# eth_part.net
KiCad netlist of a schematic drawn in Altium Designer
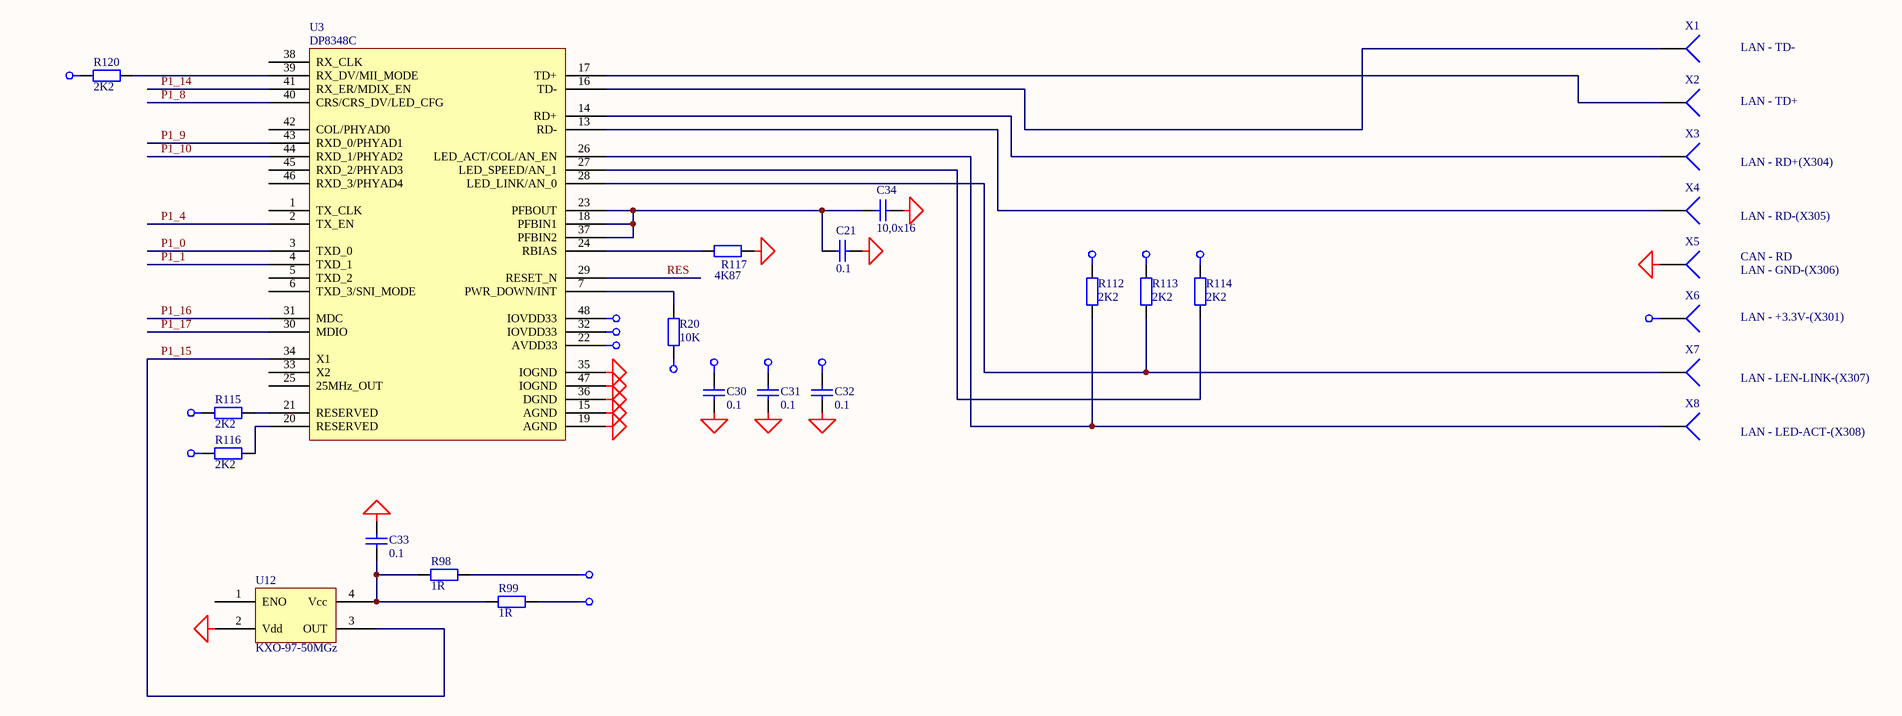
[diagram p0: eth_part.SchDoc]

(export (version "E")
  (design (tool "Eeschema 10.0.6"))
  (components
    (comp (ref "C21")
      (value "0.1")
      (footprint "C3216-1206")
      (description "Capacitor (Semiconductor SIM Model)")
      (fields (field (name "MANUFACTURER") "Generic Components") (field (name "PUBLISHER") "Altium Limited"))
      (libsource (lib "Miscellaneous Devices") (part "Cap Semi"))
    )
    (comp (ref "C30")
      (value "0.1")
      (footprint "_1206")
      (description "Capacitor (Semiconductor SIM Model)")
      (fields (field (name "MANUFACTURER") "Generic Components") (field (name "PUBLISHER") "Altium Limited"))
      (libsource (lib "Miscellaneous Devices") (part "Cap Semi"))
    )
    (comp (ref "C31")
      (value "0.1")
      (footprint "_1206")
      (description "Capacitor (Semiconductor SIM Model)")
      (fields (field (name "MANUFACTURER") "Generic Components") (field (name "PUBLISHER") "Altium Limited"))
      (libsource (lib "Miscellaneous Devices") (part "Cap Semi"))
    )
    (comp (ref "C32")
      (value "0.1")
      (footprint "_1206")
      (description "Capacitor (Semiconductor SIM Model)")
      (fields (field (name "MANUFACTURER") "Generic Components") (field (name "PUBLISHER") "Altium Limited"))
      (libsource (lib "Miscellaneous Devices") (part "Cap Semi"))
    )
    (comp (ref "C33")
      (value "0.1")
      (footprint "_1206")
      (description "Capacitor (Semiconductor SIM Model)")
      (fields (field (name "MANUFACTURER") "Generic Components") (field (name "PUBLISHER") "Altium Limited"))
      (libsource (lib "Miscellaneous Devices") (part "Cap Semi"))
    )
    (comp (ref "C34")
      (value "10,0x16")
      (footprint "C3216-1206")
      (description "Capacitor (Semiconductor SIM Model)")
      (fields (field (name "MANUFACTURER") "Generic Components") (field (name "PUBLISHER") "Altium Limited"))
      (libsource (lib "Miscellaneous Devices") (part "Cap Semi"))
    )
    (comp (ref "R20")
      (value "10K")
      (footprint "_1206")
      (description "Resistor")
      (fields (field (name "MANUFACTURER") "Generic Components") (field (name "PUBLISHER") "Altium Limited"))
      (libsource (lib "") (part "Res2_3"))
    )
    (comp (ref "R98")
      (value "1R")
      (footprint "_1206")
      (description "Resistor")
      (fields (field (name "MANUFACTURER") "Generic Components") (field (name "PUBLISHER") "Altium Limited"))
      (libsource (lib "") (part "Res2_2"))
    )
    (comp (ref "R99")
      (value "1R")
      (footprint "_1206")
      (description "Resistor")
      (fields (field (name "MANUFACTURER") "Generic Components") (field (name "PUBLISHER") "Altium Limited"))
      (libsource (lib "") (part "Res2_2"))
    )
    (comp (ref "R112")
      (value "2K2")
      (footprint "_1206")
      (description "Resistor")
      (fields (field (name "MANUFACTURER") "Generic Components") (field (name "PUBLISHER") "Altium Limited"))
      (libsource (lib "Miscellaneous Devices") (part "Res2"))
    )
    (comp (ref "R113")
      (value "2K2")
      (footprint "_1206")
      (description "Resistor")
      (fields (field (name "MANUFACTURER") "Generic Components") (field (name "PUBLISHER") "Altium Limited"))
      (libsource (lib "Miscellaneous Devices") (part "Res2"))
    )
    (comp (ref "R114")
      (value "2K2")
      (footprint "_1206")
      (description "Resistor")
      (fields (field (name "MANUFACTURER") "Generic Components") (field (name "PUBLISHER") "Altium Limited"))
      (libsource (lib "Miscellaneous Devices") (part "Res2"))
    )
    (comp (ref "R115")
      (value "2K2")
      (footprint "_1206")
      (description "Resistor")
      (fields (field (name "MANUFACTURER") "Generic Components") (field (name "PUBLISHER") "Altium Limited"))
      (libsource (lib "") (part "Res2_1"))
    )
    (comp (ref "R116")
      (value "2K2")
      (footprint "_1206")
      (description "Resistor")
      (fields (field (name "MANUFACTURER") "Generic Components") (field (name "PUBLISHER") "Altium Limited"))
      (libsource (lib "") (part "Res2_1"))
    )
    (comp (ref "R117")
      (value "4K87")
      (footprint "_1206")
      (description "Resistor")
      (fields (field (name "MANUFACTURER") "Generic Components") (field (name "PUBLISHER") "Altium Limited"))
      (libsource (lib "") (part "Res2_1"))
    )
    (comp (ref "R120")
      (value "2K2")
      (footprint "_1206")
      (description "Resistor")
      (fields (field (name "MANUFACTURER") "Generic Components") (field (name "PUBLISHER") "Altium Limited"))
      (libsource (lib "") (part "Res2_1"))
    )
    (comp (ref "U3") (value "DP8348C") (footprint "F-QFP7X7-G48/N") (libsource (lib "PAL") (part "DP8348C")))
    (comp (ref "U12") (value "KXO-97-50MGz") (footprint "KXO-97") (libsource (lib "PAL") (part "KXO-97")))
    (comp (ref "X1")
      (value "~")
      (footprint "PIN1")
      (description "Socket")
      (fields (field (name "MANUFACTURER") "Generic Components") (field (name "PUBLISHER") "Altium Limited"))
      (libsource (lib "Miscellaneous Connectors") (part "Socket"))
    )
    (comp (ref "X2")
      (value "~")
      (footprint "PIN1")
      (description "Socket")
      (fields (field (name "MANUFACTURER") "Generic Components") (field (name "PUBLISHER") "Altium Limited"))
      (libsource (lib "Miscellaneous Connectors") (part "Socket"))
    )
    (comp (ref "X3")
      (value "~")
      (footprint "PIN1")
      (description "Socket")
      (fields (field (name "MANUFACTURER") "Generic Components") (field (name "PUBLISHER") "Altium Limited"))
      (libsource (lib "Miscellaneous Connectors") (part "Socket"))
    )
    (comp (ref "X4")
      (value "~")
      (footprint "PIN1")
      (description "Socket")
      (fields (field (name "MANUFACTURER") "Generic Components") (field (name "PUBLISHER") "Altium Limited"))
      (libsource (lib "Miscellaneous Connectors") (part "Socket"))
    )
    (comp (ref "X5")
      (value "~")
      (footprint "PIN1")
      (description "Socket")
      (fields (field (name "MANUFACTURER") "Generic Components") (field (name "PUBLISHER") "Altium Limited"))
      (libsource (lib "Miscellaneous Connectors") (part "Socket"))
    )
    (comp (ref "X6")
      (value "~")
      (footprint "PIN1")
      (description "Socket")
      (fields (field (name "MANUFACTURER") "Generic Components") (field (name "PUBLISHER") "Altium Limited"))
      (libsource (lib "Miscellaneous Connectors") (part "Socket"))
    )
    (comp (ref "X7")
      (value "~")
      (footprint "PIN1")
      (description "Socket")
      (fields (field (name "MANUFACTURER") "Generic Components") (field (name "PUBLISHER") "Altium Limited"))
      (libsource (lib "Miscellaneous Connectors") (part "Socket"))
    )
    (comp (ref "X8")
      (value "~")
      (footprint "PIN1")
      (description "Socket")
      (fields (field (name "MANUFACTURER") "Generic Components") (field (name "PUBLISHER") "Altium Limited"))
      (libsource (lib "Miscellaneous Connectors") (part "Socket"))
    )
  )
  (nets
    (net (code "1") (name "+3v3") (class "Default")
      (node (ref "C30") (pin "1") (pinfunction "1_1") (pintype "passive"))
      (node (ref "C31") (pin "1") (pinfunction "1_1") (pintype "passive"))
      (node (ref "C32") (pin "1") (pinfunction "1_1") (pintype "passive"))
      (node (ref "R112") (pin "2") (pinfunction "2_2") (pintype "passive"))
      (node (ref "R113") (pin "2") (pinfunction "2_2") (pintype "passive"))
      (node (ref "R114") (pin "2") (pinfunction "2_2") (pintype "passive"))
      (node (ref "R115") (pin "2") (pinfunction "2_2") (pintype "passive"))
      (node (ref "R116") (pin "2") (pinfunction "2_2") (pintype "passive"))
      (node (ref "R120") (pin "2") (pinfunction "2_2") (pintype "passive"))
      (node (ref "R20") (pin "2") (pinfunction "2_2") (pintype "passive"))
      (node (ref "R99") (pin "2") (pinfunction "2_2") (pintype "passive"))
      (node (ref "U3") (pin "22") (pinfunction "AVDD33_22") (pintype "passive"))
      (node (ref "U3") (pin "32") (pinfunction "IOVDD33_32") (pintype "passive"))
      (node (ref "U3") (pin "48") (pinfunction "IOVDD33_48") (pintype "passive"))
      (node (ref "X6") (pin "1") (pinfunction "1_1") (pintype "passive"))
    )
    (net (code "2") (name "+5v") (class "Default")
      (node (ref "R98") (pin "2") (pinfunction "2_2") (pintype "passive"))
    )
    (net (code "3") (name "/P1_0") (class "Default")
      (node (ref "U3") (pin "3") (pinfunction "TXD_0_3") (pintype "passive"))
    )
    (net (code "4") (name "/P1_1") (class "Default")
      (node (ref "U3") (pin "4") (pinfunction "TXD_1_4") (pintype "passive"))
    )
    (net (code "5") (name "/P1_4") (class "Default")
      (node (ref "U3") (pin "2") (pinfunction "TX_EN_2") (pintype "passive"))
    )
    (net (code "6") (name "/P1_8") (class "Default")
      (node (ref "U3") (pin "40") (pinfunction "CRS/CRS_DV/LED_CFG_40") (pintype "passive"))
    )
    (net (code "7") (name "/P1_9") (class "Default")
      (node (ref "U3") (pin "43") (pinfunction "RXD_0/PHYAD1_43") (pintype "passive"))
    )
    (net (code "8") (name "/P1_10") (class "Default")
      (node (ref "U3") (pin "44") (pinfunction "RXD_1/PHYAD2_44") (pintype "passive"))
    )
    (net (code "9") (name "/P1_14") (class "Default")
      (node (ref "U3") (pin "41") (pinfunction "RX_ER/MDIX_EN_41") (pintype "passive"))
    )
    (net (code "10") (name "/P1_15") (class "Default")
      (node (ref "U12") (pin "3") (pinfunction "OUT_3") (pintype "passive"))
      (node (ref "U3") (pin "34") (pinfunction "X1_34") (pintype "passive"))
    )
    (net (code "11") (name "/P1_16") (class "Default")
      (node (ref "U3") (pin "31") (pinfunction "MDC_31") (pintype "passive"))
    )
    (net (code "12") (name "/P1_17") (class "Default")
      (node (ref "U3") (pin "30") (pinfunction "MDIO_30") (pintype "passive"))
    )
    (net (code "13") (name "/RES") (class "Default")
      (node (ref "U3") (pin "29") (pinfunction "RESET_N_29") (pintype "passive"))
    )
    (net (code "14") (name "GND") (class "Default")
      (node (ref "C21") (pin "2") (pinfunction "2_2") (pintype "passive"))
      (node (ref "C30") (pin "2") (pinfunction "2_2") (pintype "passive"))
      (node (ref "C31") (pin "2") (pinfunction "2_2") (pintype "passive"))
      (node (ref "C32") (pin "2") (pinfunction "2_2") (pintype "passive"))
      (node (ref "C33") (pin "2") (pinfunction "2_2") (pintype "passive"))
      (node (ref "C34") (pin "2") (pinfunction "2_2") (pintype "passive"))
      (node (ref "R117") (pin "1") (pinfunction "1_1") (pintype "passive"))
      (node (ref "U12") (pin "2") (pinfunction "Vdd_2") (pintype "passive"))
      (node (ref "U3") (pin "15") (pinfunction "AGND_15") (pintype "passive"))
      (node (ref "U3") (pin "19") (pinfunction "AGND_19") (pintype "passive"))
      (node (ref "U3") (pin "35") (pinfunction "IOGND_35") (pintype "passive"))
      (node (ref "U3") (pin "36") (pinfunction "DGND_36") (pintype "passive"))
      (node (ref "U3") (pin "47") (pinfunction "IOGND_47") (pintype "passive"))
      (node (ref "X5") (pin "1") (pinfunction "1_1") (pintype "passive"))
    )
    (net (code "15") (name "Net-(R115-Pad1)") (class "Default")
      (node (ref "R115") (pin "1") (pinfunction "1_1") (pintype "passive"))
      (node (ref "U3") (pin "21") (pinfunction "RESERVED_21") (pintype "passive"))
    )
    (net (code "16") (name "Net-(R116-Pad1)") (class "Default")
      (node (ref "R116") (pin "1") (pinfunction "1_1") (pintype "passive"))
      (node (ref "U3") (pin "20") (pinfunction "RESERVED_20") (pintype "passive"))
    )
    (net (code "17") (name "Net-(U3-LED_ACT{slash}COL{slash}AN_EN)") (class "Default")
      (node (ref "R112") (pin "1") (pinfunction "1_1") (pintype "passive"))
      (node (ref "U3") (pin "26") (pinfunction "LED_ACT/COL/AN_EN_26") (pintype "passive"))
      (node (ref "X8") (pin "1") (pinfunction "1_1") (pintype "passive"))
    )
    (net (code "18") (name "Net-(U3-LED_LINK{slash}AN_0)") (class "Default")
      (node (ref "R113") (pin "1") (pinfunction "1_1") (pintype "passive"))
      (node (ref "U3") (pin "28") (pinfunction "LED_LINK/AN_0_28") (pintype "passive"))
      (node (ref "X7") (pin "1") (pinfunction "1_1") (pintype "passive"))
    )
    (net (code "19") (name "Net-(U3-LED_SPEED{slash}AN_1)") (class "Default")
      (node (ref "R114") (pin "1") (pinfunction "1_1") (pintype "passive"))
      (node (ref "U3") (pin "27") (pinfunction "LED_SPEED/AN_1_27") (pintype "passive"))
    )
    (net (code "20") (name "Net-(U3-PFBIN1)") (class "Default")
      (node (ref "C21") (pin "1") (pinfunction "1_1") (pintype "passive"))
      (node (ref "C34") (pin "1") (pinfunction "1_1") (pintype "passive"))
      (node (ref "U3") (pin "18") (pinfunction "PFBIN1_18") (pintype "passive"))
      (node (ref "U3") (pin "23") (pinfunction "PFBOUT_23") (pintype "passive"))
      (node (ref "U3") (pin "37") (pinfunction "PFBIN2_37") (pintype "passive"))
    )
    (net (code "21") (name "Net-(U3-PWR_DOWN{slash}INT)") (class "Default")
      (node (ref "R20") (pin "1") (pinfunction "1_1") (pintype "passive"))
      (node (ref "U3") (pin "7") (pinfunction "PWR_DOWN/INT_7") (pintype "passive"))
    )
    (net (code "22") (name "Net-(U3-RBIAS)") (class "Default")
      (node (ref "R117") (pin "2") (pinfunction "2_2") (pintype "passive"))
      (node (ref "U3") (pin "24") (pinfunction "RBIAS_24") (pintype "passive"))
    )
    (net (code "23") (name "Net-(U3-RD+)") (class "Default")
      (node (ref "U3") (pin "14") (pinfunction "RD+_14") (pintype "passive"))
      (node (ref "X3") (pin "1") (pinfunction "1_1") (pintype "passive"))
    )
    (net (code "24") (name "Net-(U3-RD-)") (class "Default")
      (node (ref "U3") (pin "13") (pinfunction "RD-_13") (pintype "passive"))
      (node (ref "X4") (pin "1") (pinfunction "1_1") (pintype "passive"))
    )
    (net (code "25") (name "Net-(U3-RX_DV{slash}MII_MODE)") (class "Default")
      (node (ref "R120") (pin "1") (pinfunction "1_1") (pintype "passive"))
      (node (ref "U3") (pin "39") (pinfunction "RX_DV/MII_MODE_39") (pintype "passive"))
    )
    (net (code "26") (name "Net-(U3-TD+)") (class "Default")
      (node (ref "U3") (pin "17") (pinfunction "TD+_17") (pintype "passive"))
      (node (ref "X2") (pin "1") (pinfunction "1_1") (pintype "passive"))
    )
    (net (code "27") (name "Net-(U3-TD-)") (class "Default")
      (node (ref "U3") (pin "16") (pinfunction "TD-_16") (pintype "passive"))
      (node (ref "X1") (pin "1") (pinfunction "1_1") (pintype "passive"))
    )
    (net (code "28") (name "Net-(U12-Vcc)") (class "Default")
      (node (ref "C33") (pin "1") (pinfunction "1_1") (pintype "passive"))
      (node (ref "R98") (pin "1") (pinfunction "1_1") (pintype "passive"))
      (node (ref "R99") (pin "1") (pinfunction "1_1") (pintype "passive"))
      (node (ref "U12") (pin "4") (pinfunction "Vcc_4") (pintype "passive"))
    )
    (net (code "29") (name "unconnected-(U3-25MHz_OUT-Pad25)") (class "Default")
      (node (ref "U3") (pin "25") (pinfunction "25MHz_OUT_25") (pintype "passive"))
    )
    (net (code "30") (name "unconnected-(U3-COL{slash}PHYAD0-Pad42)") (class "Default")
      (node (ref "U3") (pin "42") (pinfunction "COL/PHYAD0_42") (pintype "passive"))
    )
    (net (code "31") (name "unconnected-(U3-RXD_2{slash}PHYAD3-Pad45)") (class "Default")
      (node (ref "U3") (pin "45") (pinfunction "RXD_2/PHYAD3_45") (pintype "passive"))
    )
    (net (code "32") (name "unconnected-(U3-RXD_3{slash}PHYAD4-Pad46)") (class "Default")
      (node (ref "U3") (pin "46") (pinfunction "RXD_3/PHYAD4_46") (pintype "passive"))
    )
    (net (code "33") (name "unconnected-(U3-RX_CLK-Pad38)") (class "Default")
      (node (ref "U3") (pin "38") (pinfunction "RX_CLK_38") (pintype "passive"))
    )
    (net (code "34") (name "unconnected-(U3-TXD_2-Pad5)") (class "Default")
      (node (ref "U3") (pin "5") (pinfunction "TXD_2_5") (pintype "passive"))
    )
    (net (code "35") (name "unconnected-(U3-TXD_3{slash}SNI_MODE-Pad6)") (class "Default")
      (node (ref "U3") (pin "6") (pinfunction "TXD_3/SNI_MODE_6") (pintype "passive"))
    )
    (net (code "36") (name "unconnected-(U3-TX_CLK-Pad1)") (class "Default")
      (node (ref "U3") (pin "1") (pinfunction "TX_CLK_1") (pintype "passive"))
    )
    (net (code "37") (name "unconnected-(U3-X2-Pad33)") (class "Default")
      (node (ref "U3") (pin "33") (pinfunction "X2_33") (pintype "passive"))
    )
    (net (code "38") (name "unconnected-(U12-ENO-Pad1)") (class "Default")
      (node (ref "U12") (pin "1") (pinfunction "ENO_1") (pintype "passive"))
    )
  )
)
